# IOmodule-8x_fused_35x25_fm.net
KiCad netlist of a schematic drawn in EAGLE
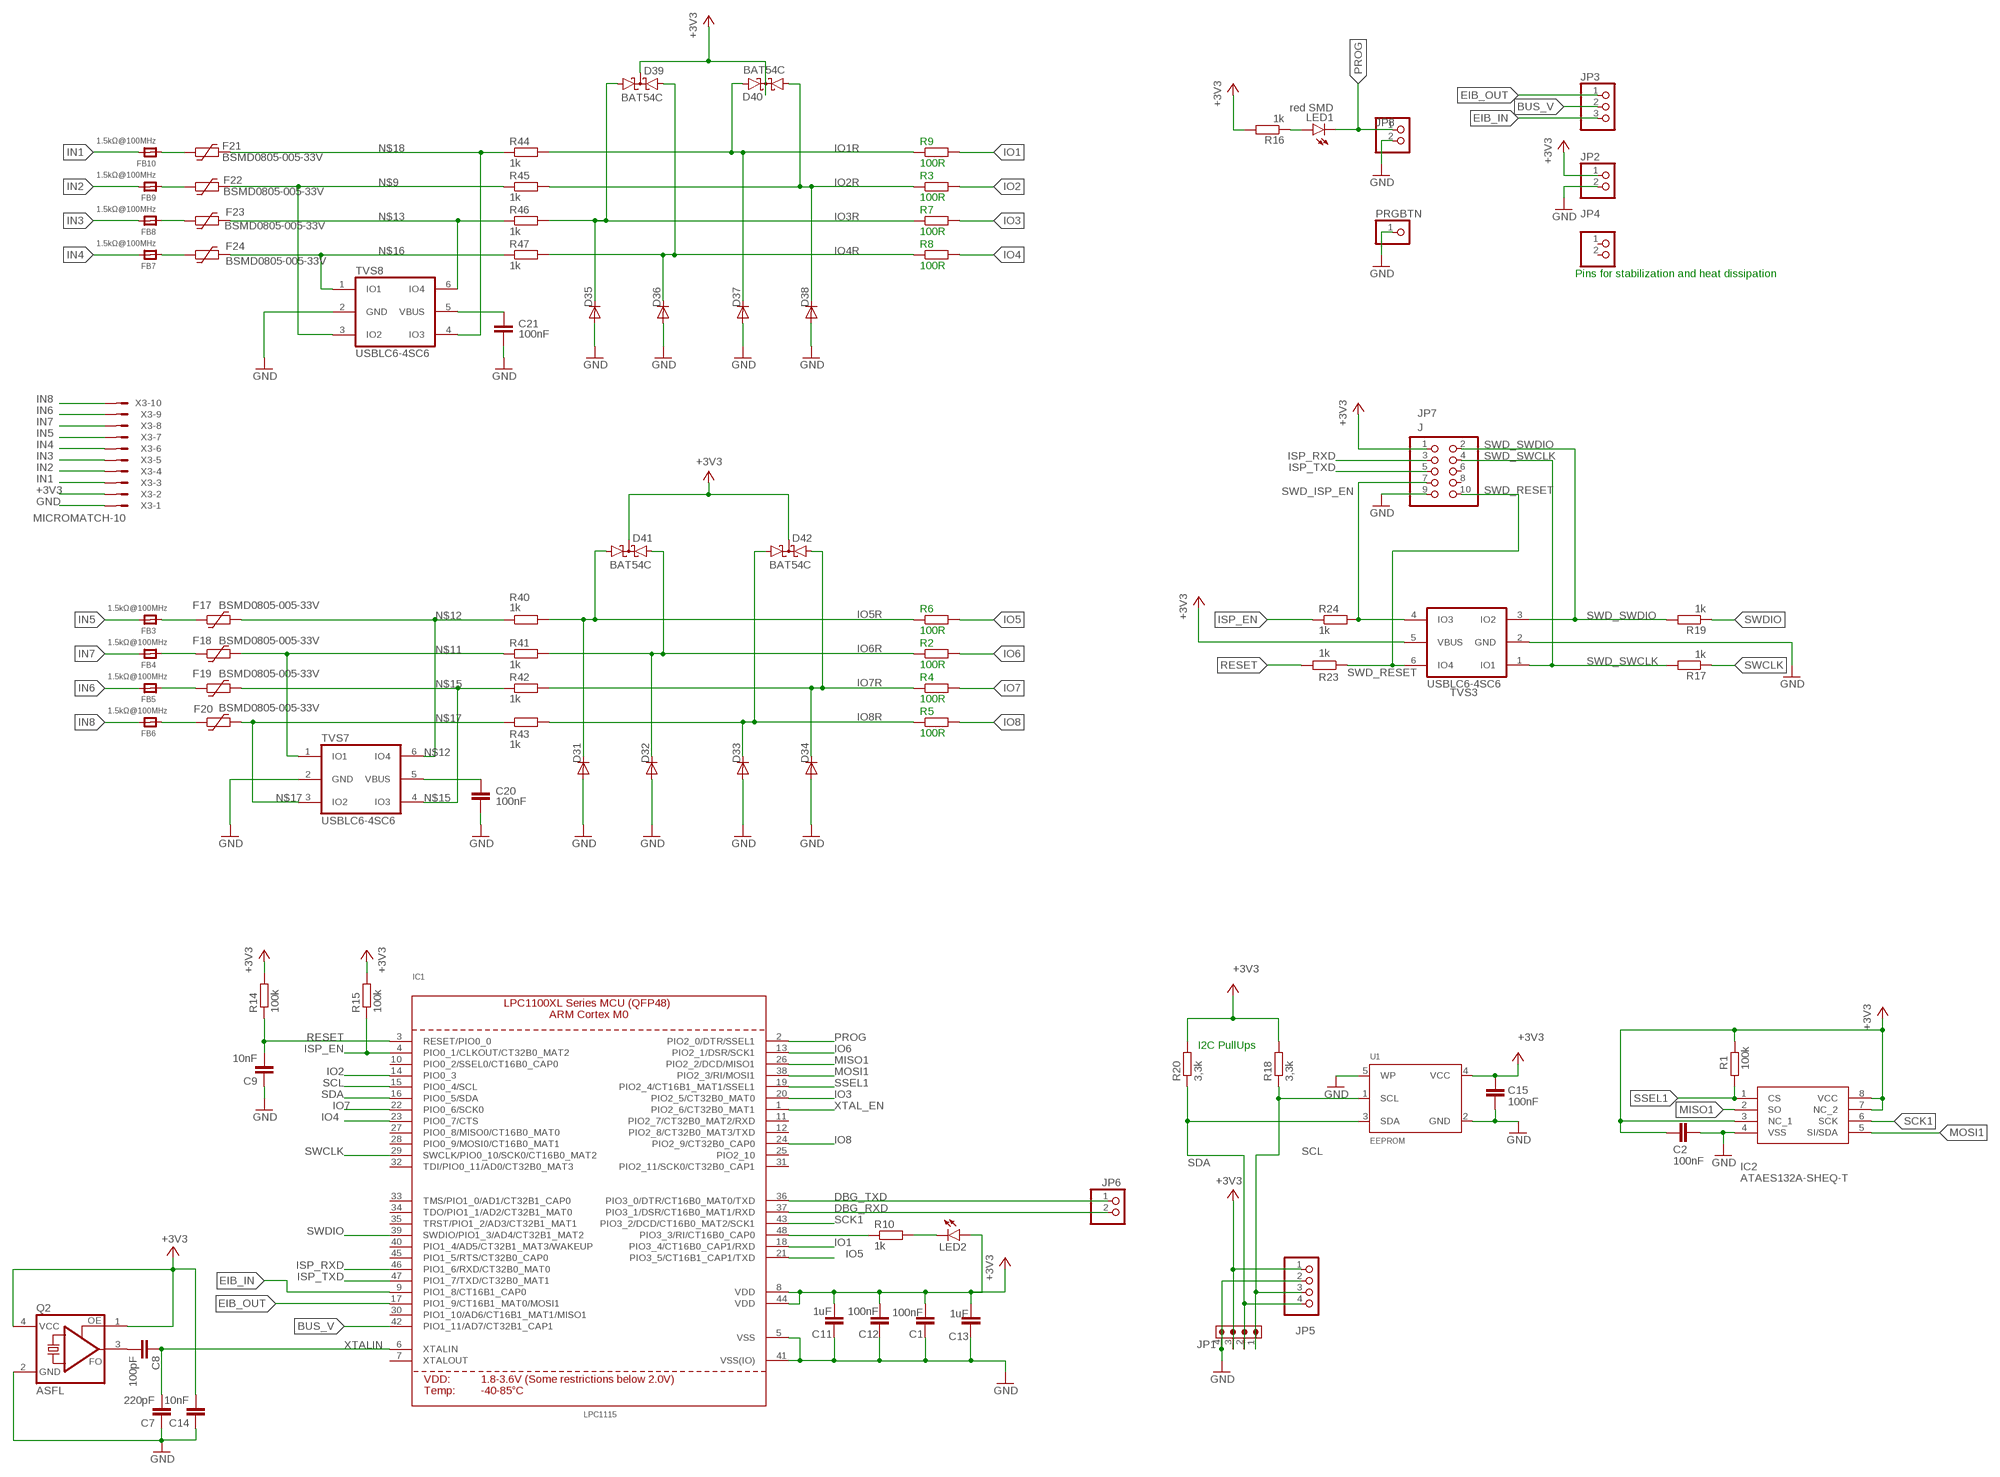
[diagram p0: schematic, sheet 1]

(export (version "E")
  (design (tool "Eeschema 10.0.6"))
  (components
    (comp (ref "C1")
      (value "100nF")
      (footprint "eagle-import:C0805")
      (libsource (lib "eagle-import") (part "C-EUC0805"))
    )
    (comp (ref "C2")
      (value "100nF")
      (footprint "eagle-import:C0805")
      (libsource (lib "eagle-import") (part "C-EUC0805"))
    )
    (comp (ref "C7")
      (value "220pF")
      (footprint "eagle-import:C0805")
      (libsource (lib "eagle-import") (part "C-EUC0805"))
    )
    (comp (ref "C8")
      (value "100pF")
      (footprint "eagle-import:C0805")
      (libsource (lib "eagle-import") (part "C-EUC0805"))
    )
    (comp (ref "C9")
      (value "10nF")
      (footprint "eagle-import:C0805")
      (libsource (lib "eagle-import") (part "C-EUC0805"))
    )
    (comp (ref "C11")
      (value "1uF")
      (footprint "eagle-import:C0805")
      (libsource (lib "eagle-import") (part "C-EUC0805"))
    )
    (comp (ref "C12")
      (value "100nF")
      (footprint "eagle-import:C0805")
      (libsource (lib "eagle-import") (part "C-EUC0805"))
    )
    (comp (ref "C13")
      (value "1uF")
      (footprint "eagle-import:C0805")
      (libsource (lib "eagle-import") (part "C-EUC0805"))
    )
    (comp (ref "C14")
      (value "10nF")
      (footprint "eagle-import:C0805")
      (libsource (lib "eagle-import") (part "C-EUC0805"))
    )
    (comp (ref "C15")
      (value "100nF")
      (footprint "eagle-import:C0805")
      (libsource (lib "eagle-import") (part "C-EUC0805"))
    )
    (comp (ref "C20")
      (value "100nF")
      (footprint "eagle-import:C0805")
      (libsource (lib "eagle-import") (part "C-EUC0805"))
    )
    (comp (ref "C21")
      (value "100nF")
      (footprint "eagle-import:C0805")
      (libsource (lib "eagle-import") (part "C-EUC0805"))
    )
    (comp (ref "D31")
      (value "DDZ9684")
      (footprint "eagle-import:SOD-123")
      (libsource (lib "eagle-import") (part "DIODESOD-123"))
    )
    (comp (ref "D32")
      (value "DDZ9684")
      (footprint "eagle-import:SOD-123")
      (libsource (lib "eagle-import") (part "DIODESOD-123"))
    )
    (comp (ref "D33")
      (value "DDZ9684")
      (footprint "eagle-import:SOD-123")
      (libsource (lib "eagle-import") (part "DIODESOD-123"))
    )
    (comp (ref "D34")
      (value "DDZ9684")
      (footprint "eagle-import:SOD-123")
      (libsource (lib "eagle-import") (part "DIODESOD-123"))
    )
    (comp (ref "D35")
      (value "DDZ9684")
      (footprint "eagle-import:SOD-123")
      (libsource (lib "eagle-import") (part "DIODESOD-123"))
    )
    (comp (ref "D36")
      (value "DDZ9684")
      (footprint "eagle-import:SOD-123")
      (libsource (lib "eagle-import") (part "DIODESOD-123"))
    )
    (comp (ref "D37")
      (value "DDZ9684")
      (footprint "eagle-import:SOD-123")
      (libsource (lib "eagle-import") (part "DIODESOD-123"))
    )
    (comp (ref "D38")
      (value "DDZ9684")
      (footprint "eagle-import:SOD-123")
      (libsource (lib "eagle-import") (part "DIODESOD-123"))
    )
    (comp (ref "D39")
      (value "BAT54C")
      (footprint "eagle-import:SOT23")
      (libsource (lib "eagle-import") (part "BAT54C"))
    )
    (comp (ref "D40")
      (value "BAT54C")
      (footprint "eagle-import:SOT23")
      (libsource (lib "eagle-import") (part "BAT54C"))
    )
    (comp (ref "D41")
      (value "BAT54C")
      (footprint "eagle-import:SOT23")
      (libsource (lib "eagle-import") (part "BAT54C"))
    )
    (comp (ref "D42")
      (value "BAT54C")
      (footprint "eagle-import:SOT23")
      (libsource (lib "eagle-import") (part "BAT54C"))
    )
    (comp (ref "F17")
      (value "BSMD0805-005-33V")
      (footprint "eagle-import:0805L")
      (fields (field (name "MF") "Littelfuse") (field (name "MPN") "0805L035"))
      (libsource (lib "eagle-import") (part "?0805L035"))
    )
    (comp (ref "F18")
      (value "BSMD0805-005-33V")
      (footprint "eagle-import:0805L")
      (fields (field (name "MF") "Littelfuse") (field (name "MPN") "0805L035"))
      (libsource (lib "eagle-import") (part "?0805L035"))
    )
    (comp (ref "F19")
      (value "BSMD0805-005-33V")
      (footprint "eagle-import:0805L")
      (fields (field (name "MF") "Littelfuse") (field (name "MPN") "0805L035"))
      (libsource (lib "eagle-import") (part "?0805L035"))
    )
    (comp (ref "F20")
      (value "BSMD0805-005-33V")
      (footprint "eagle-import:0805L")
      (fields (field (name "MF") "Littelfuse") (field (name "MPN") "0805L035"))
      (libsource (lib "eagle-import") (part "?0805L035"))
    )
    (comp (ref "F21")
      (value "BSMD0805-005-33V")
      (footprint "eagle-import:0805L")
      (fields (field (name "MF") "Littelfuse") (field (name "MPN") "0805L035"))
      (libsource (lib "eagle-import") (part "?0805L035"))
    )
    (comp (ref "F22")
      (value "BSMD0805-005-33V")
      (footprint "eagle-import:0805L")
      (fields (field (name "MF") "Littelfuse") (field (name "MPN") "0805L035"))
      (libsource (lib "eagle-import") (part "?0805L035"))
    )
    (comp (ref "F23")
      (value "BSMD0805-005-33V")
      (footprint "eagle-import:0805L")
      (fields (field (name "MF") "Littelfuse") (field (name "MPN") "0805L035"))
      (libsource (lib "eagle-import") (part "?0805L035"))
    )
    (comp (ref "F24")
      (value "BSMD0805-005-33V")
      (footprint "eagle-import:0805L")
      (fields (field (name "MF") "Littelfuse") (field (name "MPN") "0805L035"))
      (libsource (lib "eagle-import") (part "?0805L035"))
    )
    (comp (ref "FB3")
      (value "1.5kΩ@100MHz")
      (footprint "eagle-import:0805")
      (libsource (lib "eagle-import") (part "FERRITE0805"))
    )
    (comp (ref "FB4")
      (value "1.5kΩ@100MHz")
      (footprint "eagle-import:0805")
      (libsource (lib "eagle-import") (part "FERRITE0805"))
    )
    (comp (ref "FB5")
      (value "1.5kΩ@100MHz")
      (footprint "eagle-import:0805")
      (libsource (lib "eagle-import") (part "FERRITE0805"))
    )
    (comp (ref "FB6")
      (value "1.5kΩ@100MHz")
      (footprint "eagle-import:0805")
      (libsource (lib "eagle-import") (part "FERRITE0805"))
    )
    (comp (ref "FB7")
      (value "1.5kΩ@100MHz")
      (footprint "eagle-import:0805")
      (libsource (lib "eagle-import") (part "FERRITE0805"))
    )
    (comp (ref "FB8")
      (value "1.5kΩ@100MHz")
      (footprint "eagle-import:0805")
      (libsource (lib "eagle-import") (part "FERRITE0805"))
    )
    (comp (ref "FB9")
      (value "1.5kΩ@100MHz")
      (footprint "eagle-import:0805")
      (libsource (lib "eagle-import") (part "FERRITE0805"))
    )
    (comp (ref "FB10")
      (value "1.5kΩ@100MHz")
      (footprint "eagle-import:0805")
      (libsource (lib "eagle-import") (part "FERRITE0805"))
    )
    (comp (ref "IC1")
      (value "LPC1115")
      (footprint "eagle-import:LQFP48")
      (libsource (lib "eagle-import") (part "LPC1113/4/5_QFP48_XLSERIES"))
    )
    (comp (ref "IC2")
      (value "ATAES132A-SHEQ-T")
      (footprint "eagle-import:SOIC127P600X175-8N")
      (fields (field (name "MOUSER_PART_NUMBER") "556-ATAES132A-SHEQ-T"))
      (libsource (lib "eagle-import") (part "ATAES132A-SHEQ-T"))
    )
    (comp (ref "JP1")
      (value "62000411622")
      (footprint "eagle-import:62000411622")
      (libsource (lib "eagle-import") (part "62000411622"))
    )
    (comp (ref "JP2")
      (value "PINHD-1X2")
      (footprint "eagle-import:1X02")
      (libsource (lib "eagle-import") (part "PINHD-1X2"))
    )
    (comp (ref "JP3")
      (value "PINHD-1X3")
      (footprint "eagle-import:1X03")
      (libsource (lib "eagle-import") (part "PINHD-1X3"))
    )
    (comp (ref "JP4")
      (value "PINHD-1X2")
      (footprint "eagle-import:1X02")
      (libsource (lib "eagle-import") (part "PINHD-1X2"))
    )
    (comp (ref "JP5")
      (value "PINHD-1X4")
      (footprint "eagle-import:1X04")
      (libsource (lib "eagle-import") (part "PINHD-1X4"))
    )
    (comp (ref "JP6")
      (value "PINHD-1X2")
      (footprint "eagle-import:1X02")
      (libsource (lib "eagle-import") (part "PINHD-1X2"))
    )
    (comp (ref "JP7")
      (value "J")
      (footprint "eagle-import:2X05M")
      (libsource (lib "eagle-import") (part "PINHD-2X05_2.00"))
    )
    (comp (ref "JP8")
      (value "PINHD-1X2")
      (footprint "eagle-import:1X02")
      (libsource (lib "eagle-import") (part "PINHD-1X2"))
    )
    (comp (ref "LED1")
      (value "red SMD")
      (footprint "eagle-import:CHIPLED_0805")
      (libsource (lib "eagle-import") (part "LEDCHIPLED_0805"))
    )
    (comp (ref "LED2")
      (value "LEDCHIPLED_0805")
      (footprint "eagle-import:CHIPLED_0805")
      (libsource (lib "eagle-import") (part "LEDCHIPLED_0805"))
    )
    (comp (ref "PRGBTN")
      (value "PINHD-1X1")
      (footprint "eagle-import:1X01")
      (libsource (lib "eagle-import") (part "PINHD-1X1"))
    )
    (comp (ref "Q2")
      (value "ASFL")
      (footprint "eagle-import:ASF")
      (fields (field (name "MPN") "ASFLM1-50.000MHZ-C-T"))
      (libsource (lib "eagle-import") (part "ASFL"))
    )
    (comp (ref "R1")
      (value "100k")
      (footprint "eagle-import:R0805")
      (libsource (lib "eagle-import") (part "R-EU_R0805"))
    )
    (comp (ref "R2")
      (value "100R")
      (footprint "eagle-import:R0805")
      (libsource (lib "eagle-import") (part "R-EU_R0805"))
    )
    (comp (ref "R3")
      (value "100R")
      (footprint "eagle-import:R0805")
      (libsource (lib "eagle-import") (part "R-EU_R0805"))
    )
    (comp (ref "R4")
      (value "100R")
      (footprint "eagle-import:R0805")
      (libsource (lib "eagle-import") (part "R-EU_R0805"))
    )
    (comp (ref "R5")
      (value "100R")
      (footprint "eagle-import:R0805")
      (libsource (lib "eagle-import") (part "R-EU_R0805"))
    )
    (comp (ref "R6")
      (value "100R")
      (footprint "eagle-import:R0805")
      (libsource (lib "eagle-import") (part "R-EU_R0805"))
    )
    (comp (ref "R7")
      (value "100R")
      (footprint "eagle-import:R0805")
      (libsource (lib "eagle-import") (part "R-EU_R0805"))
    )
    (comp (ref "R8")
      (value "100R")
      (footprint "eagle-import:R0805")
      (libsource (lib "eagle-import") (part "R-EU_R0805"))
    )
    (comp (ref "R9")
      (value "100R")
      (footprint "eagle-import:R0805")
      (libsource (lib "eagle-import") (part "R-EU_R0805"))
    )
    (comp (ref "R10")
      (value "1k")
      (footprint "eagle-import:R0805")
      (libsource (lib "eagle-import") (part "R-EU_R0805"))
    )
    (comp (ref "R14")
      (value "100k")
      (footprint "eagle-import:R0805")
      (libsource (lib "eagle-import") (part "R-EU_R0805"))
    )
    (comp (ref "R15")
      (value "100k")
      (footprint "eagle-import:R0805")
      (libsource (lib "eagle-import") (part "R-EU_R0805"))
    )
    (comp (ref "R16")
      (value "1k")
      (footprint "eagle-import:R0805")
      (libsource (lib "eagle-import") (part "R-EU_R0805"))
    )
    (comp (ref "R17")
      (value "1k")
      (footprint "eagle-import:R0805")
      (libsource (lib "eagle-import") (part "R-EU_R0805"))
    )
    (comp (ref "R18")
      (value "3,3k")
      (footprint "eagle-import:R0805")
      (libsource (lib "eagle-import") (part "R-EU_R0805"))
    )
    (comp (ref "R19")
      (value "1k")
      (footprint "eagle-import:R0805")
      (libsource (lib "eagle-import") (part "R-EU_R0805"))
    )
    (comp (ref "R20")
      (value "3,3k")
      (footprint "eagle-import:R0805")
      (libsource (lib "eagle-import") (part "R-EU_R0805"))
    )
    (comp (ref "R23")
      (value "1k")
      (footprint "eagle-import:R0805")
      (libsource (lib "eagle-import") (part "R-EU_R0805"))
    )
    (comp (ref "R24")
      (value "1k")
      (footprint "eagle-import:R0805")
      (libsource (lib "eagle-import") (part "R-EU_R0805"))
    )
    (comp (ref "R40")
      (value "1k")
      (footprint "eagle-import:R0805")
      (libsource (lib "eagle-import") (part "R-EU_R0805"))
    )
    (comp (ref "R41")
      (value "1k")
      (footprint "eagle-import:R0805")
      (libsource (lib "eagle-import") (part "R-EU_R0805"))
    )
    (comp (ref "R42")
      (value "1k")
      (footprint "eagle-import:R0805")
      (libsource (lib "eagle-import") (part "R-EU_R0805"))
    )
    (comp (ref "R43")
      (value "1k")
      (footprint "eagle-import:R0805")
      (libsource (lib "eagle-import") (part "R-EU_R0805"))
    )
    (comp (ref "R44")
      (value "1k")
      (footprint "eagle-import:R0805")
      (libsource (lib "eagle-import") (part "R-EU_R0805"))
    )
    (comp (ref "R45")
      (value "1k")
      (footprint "eagle-import:R0805")
      (libsource (lib "eagle-import") (part "R-EU_R0805"))
    )
    (comp (ref "R46")
      (value "1k")
      (footprint "eagle-import:R0805")
      (libsource (lib "eagle-import") (part "R-EU_R0805"))
    )
    (comp (ref "R47")
      (value "1k")
      (footprint "eagle-import:R0805")
      (libsource (lib "eagle-import") (part "R-EU_R0805"))
    )
    (comp (ref "TVS3")
      (value "USBLC6-4SC6")
      (footprint "eagle-import:SOT-23-6L")
      (libsource (lib "eagle-import") (part "USBLC6-4SC6"))
    )
    (comp (ref "TVS7")
      (value "USBLC6-4SC6")
      (footprint "eagle-import:SOT-23-6L")
      (libsource (lib "eagle-import") (part "USBLC6-4SC6"))
    )
    (comp (ref "TVS8")
      (value "USBLC6-4SC6")
      (footprint "eagle-import:SOT-23-6L")
      (libsource (lib "eagle-import") (part "USBLC6-4SC6"))
    )
    (comp (ref "U1")
      (value "EEPROM")
      (footprint "eagle-import:SOT23-5")
      (libsource (lib "eagle-import") (part "EEPROM_I2C_MCP24AA32"))
    )
    (comp (ref "X3")
      (value "MICROMATCH-10")
      (footprint "eagle-import:MICROMATCH-10")
      (fields (field (name "MF") "FARNELL") (field (name "MPN") "8-215464-0"))
      (libsource (lib "eagle-import") (part "MICROMATCH-10"))
    )
  )
  (nets
    (net (code "1") (name "+3V3") (class "Default")
      (node (ref "C1") (pin "2") (pinfunction "2_2") (pintype "passive"))
      (node (ref "C11") (pin "2") (pinfunction "2_2") (pintype "passive"))
      (node (ref "C12") (pin "2") (pinfunction "2_2") (pintype "passive"))
      (node (ref "C13") (pin "2") (pinfunction "2_2") (pintype "passive"))
      (node (ref "C14") (pin "2") (pinfunction "2_2") (pintype "passive"))
      (node (ref "C15") (pin "1") (pinfunction "1_1") (pintype "passive"))
      (node (ref "C2") (pin "1") (pinfunction "1_1") (pintype "passive"))
      (node (ref "D39") (pin "3") (pinfunction "CC_3") (pintype "passive"))
      (node (ref "D40") (pin "3") (pinfunction "CC_3") (pintype "passive"))
      (node (ref "D41") (pin "3") (pinfunction "CC_3") (pintype "passive"))
      (node (ref "D42") (pin "3") (pinfunction "CC_3") (pintype "passive"))
      (node (ref "IC1") (pin "44") (pinfunction "VDD_44") (pintype "power_in"))
      (node (ref "IC1") (pin "8") (pinfunction "VDD_8") (pintype "power_in"))
      (node (ref "IC2") (pin "3") (pinfunction "NC_1_3") (pintype "bidirectional"))
      (node (ref "IC2") (pin "7") (pinfunction "NC_2_7") (pintype "bidirectional"))
      (node (ref "IC2") (pin "8") (pinfunction "VCC_8") (pintype "bidirectional"))
      (node (ref "JP1") (pin "3") (pinfunction "3_3") (pintype "passive"))
      (node (ref "JP2") (pin "1") (pinfunction "1_1") (pintype "passive"))
      (node (ref "JP5") (pin "1") (pinfunction "1_1") (pintype "passive"))
      (node (ref "JP7") (pin "1") (pinfunction "1_1") (pintype "passive"))
      (node (ref "LED2") (pin "A") (pinfunction "A_A") (pintype "passive"))
      (node (ref "Q2") (pin "1") (pinfunction "OE_1") (pintype "input"))
      (node (ref "Q2") (pin "4") (pinfunction "VCC_4") (pintype "power_in"))
      (node (ref "R1") (pin "2") (pinfunction "2_2") (pintype "passive"))
      (node (ref "R14") (pin "2") (pinfunction "2_2") (pintype "passive"))
      (node (ref "R15") (pin "2") (pinfunction "2_2") (pintype "passive"))
      (node (ref "R16") (pin "2") (pinfunction "2_2") (pintype "passive"))
      (node (ref "R18") (pin "2") (pinfunction "2_2") (pintype "passive"))
      (node (ref "R20") (pin "2") (pinfunction "2_2") (pintype "passive"))
      (node (ref "TVS3") (pin "5") (pinfunction "VBUS_5") (pintype "bidirectional"))
      (node (ref "U1") (pin "4") (pinfunction "VCC_4") (pintype "bidirectional"))
      (node (ref "X3") (pin "2") (pinfunction "S_2") (pintype "passive"))
    )
    (net (code "2") (name "/DBG_RXD") (class "Default")
      (node (ref "IC1") (pin "37") (pinfunction "PIO3_1/DSR/CT16B0_MAT1/RXD_37") (pintype "bidirectional"))
      (node (ref "JP6") (pin "2") (pinfunction "2_2") (pintype "passive"))
    )
    (net (code "3") (name "/DBG_TXD") (class "Default")
      (node (ref "IC1") (pin "36") (pinfunction "PIO3_0/DTR/CT16B0_MAT0/TXD_36") (pintype "bidirectional"))
      (node (ref "JP6") (pin "1") (pinfunction "1_1") (pintype "passive"))
    )
    (net (code "4") (name "/IO1R") (class "Default")
      (node (ref "D37") (pin "C") (pinfunction "C_C") (pintype "passive"))
      (node (ref "D40") (pin "2") (pinfunction "A2_2") (pintype "passive"))
      (node (ref "R44") (pin "2") (pinfunction "2_2") (pintype "passive"))
      (node (ref "R9") (pin "1") (pinfunction "1_1") (pintype "passive"))
    )
    (net (code "5") (name "/IO2R") (class "Default")
      (node (ref "D38") (pin "C") (pinfunction "C_C") (pintype "passive"))
      (node (ref "D40") (pin "1") (pinfunction "A1_1") (pintype "passive"))
      (node (ref "R3") (pin "1") (pinfunction "1_1") (pintype "passive"))
      (node (ref "R45") (pin "2") (pinfunction "2_2") (pintype "passive"))
    )
    (net (code "6") (name "/IO3R") (class "Default")
      (node (ref "D35") (pin "C") (pinfunction "C_C") (pintype "passive"))
      (node (ref "D39") (pin "1") (pinfunction "A1_1") (pintype "passive"))
      (node (ref "R46") (pin "2") (pinfunction "2_2") (pintype "passive"))
      (node (ref "R7") (pin "1") (pinfunction "1_1") (pintype "passive"))
    )
    (net (code "7") (name "/IO4R") (class "Default")
      (node (ref "D36") (pin "C") (pinfunction "C_C") (pintype "passive"))
      (node (ref "D39") (pin "2") (pinfunction "A2_2") (pintype "passive"))
      (node (ref "R47") (pin "2") (pinfunction "2_2") (pintype "passive"))
      (node (ref "R8") (pin "1") (pinfunction "1_1") (pintype "passive"))
    )
    (net (code "8") (name "/IO5R") (class "Default")
      (node (ref "D31") (pin "C") (pinfunction "C_C") (pintype "passive"))
      (node (ref "D41") (pin "1") (pinfunction "A1_1") (pintype "passive"))
      (node (ref "R40") (pin "2") (pinfunction "2_2") (pintype "passive"))
      (node (ref "R6") (pin "1") (pinfunction "1_1") (pintype "passive"))
    )
    (net (code "9") (name "/IO6R") (class "Default")
      (node (ref "D32") (pin "C") (pinfunction "C_C") (pintype "passive"))
      (node (ref "D41") (pin "2") (pinfunction "A2_2") (pintype "passive"))
      (node (ref "R2") (pin "1") (pinfunction "1_1") (pintype "passive"))
      (node (ref "R41") (pin "2") (pinfunction "2_2") (pintype "passive"))
    )
    (net (code "10") (name "/IO7R") (class "Default")
      (node (ref "D34") (pin "C") (pinfunction "C_C") (pintype "passive"))
      (node (ref "D42") (pin "2") (pinfunction "A2_2") (pintype "passive"))
      (node (ref "R4") (pin "1") (pinfunction "1_1") (pintype "passive"))
      (node (ref "R42") (pin "2") (pinfunction "2_2") (pintype "passive"))
    )
    (net (code "11") (name "/IO8R") (class "Default")
      (node (ref "D33") (pin "C") (pinfunction "C_C") (pintype "passive"))
      (node (ref "D42") (pin "1") (pinfunction "A1_1") (pintype "passive"))
      (node (ref "R43") (pin "2") (pinfunction "2_2") (pintype "passive"))
      (node (ref "R5") (pin "1") (pinfunction "1_1") (pintype "passive"))
    )
    (net (code "12") (name "/ISP_RXD") (class "Default")
      (node (ref "IC1") (pin "46") (pinfunction "PIO1_6/RXD/CT32B0_MAT0_46") (pintype "bidirectional"))
      (node (ref "JP7") (pin "3") (pinfunction "3_3") (pintype "passive"))
    )
    (net (code "13") (name "/ISP_TXD") (class "Default")
      (node (ref "IC1") (pin "47") (pinfunction "PIO1_7/TXD/CT32B0_MAT1_47") (pintype "bidirectional"))
      (node (ref "JP7") (pin "5") (pinfunction "5_5") (pintype "passive"))
    )
    (net (code "14") (name "/N$9") (class "Default")
      (node (ref "F22") (pin "2") (pinfunction "2_2") (pintype "passive"))
      (node (ref "R45") (pin "1") (pinfunction "1_1") (pintype "passive"))
      (node (ref "TVS8") (pin "3") (pinfunction "IO2_3") (pintype "bidirectional"))
    )
    (net (code "15") (name "/N$11") (class "Default")
      (node (ref "F18") (pin "2") (pinfunction "2_2") (pintype "passive"))
      (node (ref "R41") (pin "1") (pinfunction "1_1") (pintype "passive"))
      (node (ref "TVS7") (pin "1") (pinfunction "IO1_1") (pintype "bidirectional"))
    )
    (net (code "16") (name "/N$12") (class "Default")
      (node (ref "F17") (pin "2") (pinfunction "2_2") (pintype "passive"))
      (node (ref "R40") (pin "1") (pinfunction "1_1") (pintype "passive"))
      (node (ref "TVS7") (pin "6") (pinfunction "IO4_6") (pintype "bidirectional"))
    )
    (net (code "17") (name "/N$13") (class "Default")
      (node (ref "F23") (pin "2") (pinfunction "2_2") (pintype "passive"))
      (node (ref "R46") (pin "1") (pinfunction "1_1") (pintype "passive"))
      (node (ref "TVS8") (pin "6") (pinfunction "IO4_6") (pintype "bidirectional"))
    )
    (net (code "18") (name "/N$15") (class "Default")
      (node (ref "F19") (pin "2") (pinfunction "2_2") (pintype "passive"))
      (node (ref "R42") (pin "1") (pinfunction "1_1") (pintype "passive"))
      (node (ref "TVS7") (pin "4") (pinfunction "IO3_4") (pintype "bidirectional"))
    )
    (net (code "19") (name "/N$16") (class "Default")
      (node (ref "F24") (pin "2") (pinfunction "2_2") (pintype "passive"))
      (node (ref "R47") (pin "1") (pinfunction "1_1") (pintype "passive"))
      (node (ref "TVS8") (pin "1") (pinfunction "IO1_1") (pintype "bidirectional"))
    )
    (net (code "20") (name "/N$17") (class "Default")
      (node (ref "F20") (pin "2") (pinfunction "2_2") (pintype "passive"))
      (node (ref "R43") (pin "1") (pinfunction "1_1") (pintype "passive"))
      (node (ref "TVS7") (pin "3") (pinfunction "IO2_3") (pintype "bidirectional"))
    )
    (net (code "21") (name "/N$18") (class "Default")
      (node (ref "F21") (pin "2") (pinfunction "2_2") (pintype "passive"))
      (node (ref "R44") (pin "1") (pinfunction "1_1") (pintype "passive"))
      (node (ref "TVS8") (pin "4") (pinfunction "IO3_4") (pintype "bidirectional"))
    )
    (net (code "22") (name "/SCL") (class "Default")
      (node (ref "IC1") (pin "15") (pinfunction "PIO0_4/SCL_15") (pintype "bidirectional"))
      (node (ref "JP1") (pin "1") (pinfunction "1_1") (pintype "passive"))
      (node (ref "JP5") (pin "3") (pinfunction "3_3") (pintype "passive"))
      (node (ref "R18") (pin "1") (pinfunction "1_1") (pintype "passive"))
      (node (ref "U1") (pin "1") (pinfunction "SCL_1") (pintype "bidirectional"))
    )
    (net (code "23") (name "/SDA") (class "Default")
      (node (ref "IC1") (pin "16") (pinfunction "PIO0_5/SDA_16") (pintype "bidirectional"))
      (node (ref "JP1") (pin "2") (pinfunction "2_2") (pintype "passive"))
      (node (ref "JP5") (pin "4") (pinfunction "4_4") (pintype "passive"))
      (node (ref "R20") (pin "1") (pinfunction "1_1") (pintype "passive"))
      (node (ref "U1") (pin "3") (pinfunction "SDA_3") (pintype "bidirectional"))
    )
    (net (code "24") (name "/SWD_ISP_EN") (class "Default")
      (node (ref "JP7") (pin "7") (pinfunction "7_7") (pintype "passive"))
      (node (ref "R24") (pin "2") (pinfunction "2_2") (pintype "passive"))
      (node (ref "TVS3") (pin "4") (pinfunction "IO3_4") (pintype "bidirectional"))
    )
    (net (code "25") (name "/SWD_RESET") (class "Default")
      (node (ref "JP7") (pin "10") (pinfunction "10_10") (pintype "passive"))
      (node (ref "R23") (pin "1") (pinfunction "1_1") (pintype "passive"))
      (node (ref "TVS3") (pin "6") (pinfunction "IO4_6") (pintype "bidirectional"))
    )
    (net (code "26") (name "/SWD_SWCLK") (class "Default")
      (node (ref "JP7") (pin "4") (pinfunction "4_4") (pintype "passive"))
      (node (ref "R17") (pin "2") (pinfunction "2_2") (pintype "passive"))
      (node (ref "TVS3") (pin "1") (pinfunction "IO1_1") (pintype "bidirectional"))
    )
    (net (code "27") (name "/SWD_SWDIO") (class "Default")
      (node (ref "JP7") (pin "2") (pinfunction "2_2") (pintype "passive"))
      (node (ref "R19") (pin "2") (pinfunction "2_2") (pintype "passive"))
      (node (ref "TVS3") (pin "3") (pinfunction "IO2_3") (pintype "bidirectional"))
    )
    (net (code "28") (name "/XTALIN") (class "Default")
      (node (ref "C7") (pin "2") (pinfunction "2_2") (pintype "passive"))
      (node (ref "C8") (pin "1") (pinfunction "1_1") (pintype "passive"))
      (node (ref "IC1") (pin "6") (pinfunction "XTALIN_6") (pintype "input"))
    )
    (net (code "29") (name "/XTAL_EN") (class "Default")
      (node (ref "IC1") (pin "1") (pinfunction "PIO2_6/CT32B0_MAT1_1") (pintype "bidirectional"))
    )
    (net (code "30") (name "BUS_V") (class "Default")
      (node (ref "IC1") (pin "42") (pinfunction "PIO1_11/AD7/CT32B1_CAP1_42") (pintype "bidirectional"))
      (node (ref "JP3") (pin "2") (pinfunction "2_2") (pintype "passive"))
    )
    (net (code "31") (name "EIB_IN") (class "Default")
      (node (ref "IC1") (pin "9") (pinfunction "PIO1_8/CT16B1_CAP0_9") (pintype "bidirectional"))
      (node (ref "JP3") (pin "3") (pinfunction "3_3") (pintype "passive"))
    )
    (net (code "32") (name "EIB_OUT") (class "Default")
      (node (ref "IC1") (pin "17") (pinfunction "PIO1_9/CT16B1_MAT0/MOSI1_17") (pintype "bidirectional"))
      (node (ref "JP3") (pin "1") (pinfunction "1_1") (pintype "passive"))
    )
    (net (code "33") (name "GND") (class "Default")
      (node (ref "C1") (pin "1") (pinfunction "1_1") (pintype "passive"))
      (node (ref "C11") (pin "1") (pinfunction "1_1") (pintype "passive"))
      (node (ref "C12") (pin "1") (pinfunction "1_1") (pintype "passive"))
      (node (ref "C13") (pin "1") (pinfunction "1_1") (pintype "passive"))
      (node (ref "C14") (pin "1") (pinfunction "1_1") (pintype "passive"))
      (node (ref "C15") (pin "2") (pinfunction "2_2") (pintype "passive"))
      (node (ref "C2") (pin "2") (pinfunction "2_2") (pintype "passive"))
      (node (ref "C20") (pin "1") (pinfunction "1_1") (pintype "passive"))
      (node (ref "C21") (pin "1") (pinfunction "1_1") (pintype "passive"))
      (node (ref "C7") (pin "1") (pinfunction "1_1") (pintype "passive"))
      (node (ref "C9") (pin "1") (pinfunction "1_1") (pintype "passive"))
      (node (ref "D31") (pin "A") (pinfunction "A_A") (pintype "passive"))
      (node (ref "D32") (pin "A") (pinfunction "A_A") (pintype "passive"))
      (node (ref "D33") (pin "A") (pinfunction "A_A") (pintype "passive"))
      (node (ref "D34") (pin "A") (pinfunction "A_A") (pintype "passive"))
      (node (ref "D35") (pin "A") (pinfunction "A_A") (pintype "passive"))
      (node (ref "D36") (pin "A") (pinfunction "A_A") (pintype "passive"))
      (node (ref "D37") (pin "A") (pinfunction "A_A") (pintype "passive"))
      (node (ref "D38") (pin "A") (pinfunction "A_A") (pintype "passive"))
      (node (ref "IC1") (pin "41") (pinfunction "VSS(IO)_41") (pintype "power_in"))
      (node (ref "IC1") (pin "5") (pinfunction "VSS_5") (pintype "power_in"))
      (node (ref "IC2") (pin "4") (pinfunction "VSS_4") (pintype "bidirectional"))
      (node (ref "JP1") (pin "4") (pinfunction "4_4") (pintype "passive"))
      (node (ref "JP2") (pin "2") (pinfunction "2_2") (pintype "passive"))
      (node (ref "JP5") (pin "2") (pinfunction "2_2") (pintype "passive"))
      (node (ref "JP7") (pin "9") (pinfunction "9_9") (pintype "passive"))
      (node (ref "JP8") (pin "2") (pinfunction "2_2") (pintype "passive"))
      (node (ref "PRGBTN") (pin "1") (pinfunction "1_1") (pintype "passive"))
      (node (ref "Q2") (pin "2") (pinfunction "GND_2") (pintype "power_in"))
      (node (ref "TVS3") (pin "2") (pinfunction "GND_2") (pintype "bidirectional"))
      (node (ref "TVS7") (pin "2") (pinfunction "GND_2") (pintype "bidirectional"))
      (node (ref "TVS8") (pin "2") (pinfunction "GND_2") (pintype "bidirectional"))
      (node (ref "U1") (pin "2") (pinfunction "GND_2") (pintype "bidirectional"))
      (node (ref "U1") (pin "5") (pinfunction "WP_5") (pintype "bidirectional"))
      (node (ref "X3") (pin "1") (pinfunction "S_1") (pintype "passive"))
    )
    (net (code "34") (name "IN1") (class "Default")
      (node (ref "FB10") (pin "2") (pinfunction "P$2_2") (pintype "passive"))
      (node (ref "X3") (pin "3") (pinfunction "S_3") (pintype "passive"))
    )
    (net (code "35") (name "IN2") (class "Default")
      (node (ref "FB9") (pin "2") (pinfunction "P$2_2") (pintype "passive"))
      (node (ref "X3") (pin "4") (pinfunction "S_4") (pintype "passive"))
    )
    (net (code "36") (name "IN3") (class "Default")
      (node (ref "FB8") (pin "2") (pinfunction "P$2_2") (pintype "passive"))
      (node (ref "X3") (pin "5") (pinfunction "S_5") (pintype "passive"))
    )
    (net (code "37") (name "IN4") (class "Default")
      (node (ref "FB7") (pin "2") (pinfunction "P$2_2") (pintype "passive"))
      (node (ref "X3") (pin "6") (pinfunction "S_6") (pintype "passive"))
    )
    (net (code "38") (name "IN5") (class "Default")
      (node (ref "FB3") (pin "2") (pinfunction "P$2_2") (pintype "passive"))
      (node (ref "X3") (pin "7") (pinfunction "S_7") (pintype "passive"))
    )
    (net (code "39") (name "IN6") (class "Default")
      (node (ref "FB5") (pin "2") (pinfunction "P$2_2") (pintype "passive"))
      (node (ref "X3") (pin "9") (pinfunction "S_9") (pintype "passive"))
    )
    (net (code "40") (name "IN7") (class "Default")
      (node (ref "FB4") (pin "2") (pinfunction "P$2_2") (pintype "passive"))
      (node (ref "X3") (pin "8") (pinfunction "S_8") (pintype "passive"))
    )
    (net (code "41") (name "IN8") (class "Default")
      (node (ref "FB6") (pin "2") (pinfunction "P$2_2") (pintype "passive"))
      (node (ref "X3") (pin "10") (pinfunction "S_10") (pintype "passive"))
    )
    (net (code "42") (name "IO1") (class "Default")
      (node (ref "IC1") (pin "18") (pinfunction "PIO3_4/CT16B0_CAP1/RXD_18") (pintype "bidirectional"))
      (node (ref "R9") (pin "2") (pinfunction "2_2") (pintype "passive"))
    )
    (net (code "43") (name "IO2") (class "Default")
      (node (ref "IC1") (pin "14") (pinfunction "PIO0_3_14") (pintype "bidirectional"))
      (node (ref "R3") (pin "2") (pinfunction "2_2") (pintype "passive"))
    )
    (net (code "44") (name "IO3") (class "Default")
      (node (ref "IC1") (pin "20") (pinfunction "PIO2_5/CT32B0_MAT0_20") (pintype "bidirectional"))
      (node (ref "R7") (pin "2") (pinfunction "2_2") (pintype "passive"))
    )
    (net (code "45") (name "IO4") (class "Default")
      (node (ref "IC1") (pin "23") (pinfunction "PIO0_7/CTS_23") (pintype "bidirectional"))
      (node (ref "R8") (pin "2") (pinfunction "2_2") (pintype "passive"))
    )
    (net (code "46") (name "IO5") (class "Default")
      (node (ref "IC1") (pin "21") (pinfunction "PIO3_5/CT16B1_CAP1/TXD_21") (pintype "bidirectional"))
      (node (ref "R6") (pin "2") (pinfunction "2_2") (pintype "passive"))
    )
    (net (code "47") (name "IO6") (class "Default")
      (node (ref "IC1") (pin "13") (pinfunction "PIO2_1/DSR/SCK1_13") (pintype "bidirectional"))
      (node (ref "R2") (pin "2") (pinfunction "2_2") (pintype "passive"))
    )
    (net (code "48") (name "IO7") (class "Default")
      (node (ref "IC1") (pin "22") (pinfunction "PIO0_6/SCK0_22") (pintype "bidirectional"))
      (node (ref "R4") (pin "2") (pinfunction "2_2") (pintype "passive"))
    )
    (net (code "49") (name "IO8") (class "Default")
      (node (ref "IC1") (pin "24") (pinfunction "PIO2_9/CT32B0_CAP0_24") (pintype "bidirectional"))
      (node (ref "R5") (pin "2") (pinfunction "2_2") (pintype "passive"))
    )
    (net (code "50") (name "ISP_EN") (class "Default")
      (node (ref "IC1") (pin "4") (pinfunction "PIO0_1/CLKOUT/CT32B0_MAT2_4") (pintype "bidirectional"))
      (node (ref "R15") (pin "1") (pinfunction "1_1") (pintype "passive"))
      (node (ref "R24") (pin "1") (pinfunction "1_1") (pintype "passive"))
    )
    (net (code "51") (name "MISO1") (class "Default")
      (node (ref "IC1") (pin "26") (pinfunction "PIO2_2/DCD/MISO1_26") (pintype "bidirectional"))
      (node (ref "IC2") (pin "2") (pinfunction "SO_2") (pintype "bidirectional"))
    )
    (net (code "52") (name "MOSI1") (class "Default")
      (node (ref "IC1") (pin "38") (pinfunction "PIO2_3/RI/MOSI1_38") (pintype "bidirectional"))
      (node (ref "IC2") (pin "5") (pinfunction "SI/SDA_5") (pintype "bidirectional"))
    )
    (net (code "53") (name "Net-(FB3-P$1)") (class "Default")
      (node (ref "F17") (pin "1") (pinfunction "1_1") (pintype "passive"))
      (node (ref "FB3") (pin "1") (pinfunction "P$1_1") (pintype "passive"))
    )
    (net (code "54") (name "Net-(FB4-P$1)") (class "Default")
      (node (ref "F18") (pin "1") (pinfunction "1_1") (pintype "passive"))
      (node (ref "FB4") (pin "1") (pinfunction "P$1_1") (pintype "passive"))
    )
    (net (code "55") (name "Net-(FB5-P$1)") (class "Default")
      (node (ref "F19") (pin "1") (pinfunction "1_1") (pintype "passive"))
      (node (ref "FB5") (pin "1") (pinfunction "P$1_1") (pintype "passive"))
    )
    (net (code "56") (name "Net-(FB6-P$1)") (class "Default")
      (node (ref "F20") (pin "1") (pinfunction "1_1") (pintype "passive"))
      (node (ref "FB6") (pin "1") (pinfunction "P$1_1") (pintype "passive"))
    )
    (net (code "57") (name "Net-(FB7-P$1)") (class "Default")
      (node (ref "F24") (pin "1") (pinfunction "1_1") (pintype "passive"))
      (node (ref "FB7") (pin "1") (pinfunction "P$1_1") (pintype "passive"))
    )
    (net (code "58") (name "Net-(FB8-P$1)") (class "Default")
      (node (ref "F23") (pin "1") (pinfunction "1_1") (pintype "passive"))
      (node (ref "FB8") (pin "1") (pinfunction "P$1_1") (pintype "passive"))
    )
    (net (code "59") (name "Net-(FB9-P$1)") (class "Default")
      (node (ref "F22") (pin "1") (pinfunction "1_1") (pintype "passive"))
      (node (ref "FB9") (pin "1") (pinfunction "P$1_1") (pintype "passive"))
    )
    (net (code "60") (name "Net-(FB10-P$1)") (class "Default")
      (node (ref "F21") (pin "1") (pinfunction "1_1") (pintype "passive"))
      (node (ref "FB10") (pin "1") (pinfunction "P$1_1") (pintype "passive"))
    )
    (net (code "61") (name "Net-(IC1-PIO3_3{slash}RI{slash}CT16B0_CAP0)") (class "Default")
      (node (ref "IC1") (pin "48") (pinfunction "PIO3_3/RI/CT16B0_CAP0_48") (pintype "bidirectional"))
      (node (ref "R10") (pin "1") (pinfunction "1_1") (pintype "passive"))
    )
    (net (code "62") (name "Net-(LED1-PadA)") (class "Default")
      (node (ref "LED1") (pin "A") (pinfunction "A_A") (pintype "passive"))
      (node (ref "R16") (pin "1") (pinfunction "1_1") (pintype "passive"))
    )
    (net (code "63") (name "Net-(LED2-PadC)") (class "Default")
      (node (ref "LED2") (pin "C") (pinfunction "C_C") (pintype "passive"))
      (node (ref "R10") (pin "2") (pinfunction "2_2") (pintype "passive"))
    )
    (net (code "64") (name "Net-(Q2-FO)") (class "Default")
      (node (ref "C8") (pin "2") (pinfunction "2_2") (pintype "passive"))
      (node (ref "Q2") (pin "3") (pinfunction "FO_3") (pintype "output"))
    )
    (net (code "65") (name "Net-(TVS7-VBUS)") (class "Default")
      (node (ref "C20") (pin "2") (pinfunction "2_2") (pintype "passive"))
      (node (ref "TVS7") (pin "5") (pinfunction "VBUS_5") (pintype "bidirectional"))
    )
    (net (code "66") (name "Net-(TVS8-VBUS)") (class "Default")
      (node (ref "C21") (pin "2") (pinfunction "2_2") (pintype "passive"))
      (node (ref "TVS8") (pin "5") (pinfunction "VBUS_5") (pintype "bidirectional"))
    )
    (net (code "67") (name "PROG") (class "Default")
      (node (ref "IC1") (pin "2") (pinfunction "PIO2_0/DTR/SSEL1_2") (pintype "bidirectional"))
      (node (ref "JP8") (pin "1") (pinfunction "1_1") (pintype "passive"))
      (node (ref "LED1") (pin "C") (pinfunction "C_C") (pintype "passive"))
    )
    (net (code "68") (name "RESET") (class "Default")
      (node (ref "C9") (pin "2") (pinfunction "2_2") (pintype "passive"))
      (node (ref "IC1") (pin "3") (pinfunction "RESET/PIO0_0_3") (pintype "bidirectional"))
      (node (ref "R14") (pin "1") (pinfunction "1_1") (pintype "passive"))
      (node (ref "R23") (pin "2") (pinfunction "2_2") (pintype "passive"))
    )
    (net (code "69") (name "SCK1") (class "Default")
      (node (ref "IC1") (pin "43") (pinfunction "PIO3_2/DCD/CT16B0_MAT2/SCK1_43") (pintype "bidirectional"))
      (node (ref "IC2") (pin "6") (pinfunction "SCK_6") (pintype "bidirectional"))
    )
    (net (code "70") (name "SSEL1") (class "Default")
      (node (ref "IC1") (pin "19") (pinfunction "PIO2_4/CT16B1_MAT1/SSEL1_19") (pintype "bidirectional"))
      (node (ref "IC2") (pin "1") (pinfunction "CS_1") (pintype "bidirectional"))
      (node (ref "R1") (pin "1") (pinfunction "1_1") (pintype "passive"))
    )
    (net (code "71") (name "SWCLK") (class "Default")
      (node (ref "IC1") (pin "29") (pinfunction "SWCLK/PIO0_10/SCK0/CT16B0_MAT2_29") (pintype "bidirectional"))
      (node (ref "R17") (pin "1") (pinfunction "1_1") (pintype "passive"))
    )
    (net (code "72") (name "SWDIO") (class "Default")
      (node (ref "IC1") (pin "39") (pinfunction "SWDIO/PIO1_3/AD4/CT32B1_MAT2_39") (pintype "bidirectional"))
      (node (ref "R19") (pin "1") (pinfunction "1_1") (pintype "passive"))
    )
    (net (code "73") (name "unconnected-(IC1-PIO0_2{slash}SSEL0{slash}CT16B0_CAP0-Pad10)") (class "Default")
      (node (ref "IC1") (pin "10") (pinfunction "PIO0_2/SSEL0/CT16B0_CAP0_10") (pintype "bidirectional"))
    )
    (net (code "74") (name "unconnected-(IC1-PIO0_8{slash}MISO0{slash}CT16B0_MAT0-Pad27)") (class "Default")
      (node (ref "IC1") (pin "27") (pinfunction "PIO0_8/MISO0/CT16B0_MAT0_27") (pintype "bidirectional"))
    )
    (net (code "75") (name "unconnected-(IC1-PIO0_9{slash}MOSI0{slash}CT16B0_MAT1-Pad28)") (class "Default")
      (node (ref "IC1") (pin "28") (pinfunction "PIO0_9/MOSI0/CT16B0_MAT1_28") (pintype "bidirectional"))
    )
    (net (code "76") (name "unconnected-(IC1-PIO1_4{slash}AD5{slash}CT32B1_MAT3{slash}WAKEUP-Pad40)") (class "Default")
      (node (ref "IC1") (pin "40") (pinfunction "PIO1_4/AD5/CT32B1_MAT3/WAKEUP_40") (pintype "bidirectional"))
    )
    (net (code "77") (name "unconnected-(IC1-PIO1_5{slash}RTS{slash}CT32B0_CAP0-Pad45)") (class "Default")
      (node (ref "IC1") (pin "45") (pinfunction "PIO1_5/RTS/CT32B0_CAP0_45") (pintype "bidirectional"))
    )
    (net (code "78") (name "unconnected-(IC1-PIO1_10{slash}AD6{slash}CT16B1_MAT1{slash}MISO1-Pad30)") (class "Default")
      (node (ref "IC1") (pin "30") (pinfunction "PIO1_10/AD6/CT16B1_MAT1/MISO1_30") (pintype "bidirectional"))
    )
    (net (code "79") (name "unconnected-(IC1-PIO2_7{slash}CT32B0_MAT2{slash}RXD-Pad11)") (class "Default")
      (node (ref "IC1") (pin "11") (pinfunction "PIO2_7/CT32B0_MAT2/RXD_11") (pintype "bidirectional"))
    )
    (net (code "80") (name "unconnected-(IC1-PIO2_8{slash}CT32B0_MAT3{slash}TXD-Pad12)") (class "Default")
      (node (ref "IC1") (pin "12") (pinfunction "PIO2_8/CT32B0_MAT3/TXD_12") (pintype "bidirectional"))
    )
    (net (code "81") (name "unconnected-(IC1-PIO2_10-Pad25)") (class "Default")
      (node (ref "IC1") (pin "25") (pinfunction "PIO2_10_25") (pintype "bidirectional"))
    )
    (net (code "82") (name "unconnected-(IC1-PIO2_11{slash}SCK0{slash}CT32B0_CAP1-Pad31)") (class "Default")
      (node (ref "IC1") (pin "31") (pinfunction "PIO2_11/SCK0/CT32B0_CAP1_31") (pintype "bidirectional"))
    )
    (net (code "83") (name "unconnected-(IC1-TDI{slash}PIO0_11{slash}AD0{slash}CT32B0_MAT3-Pad32)") (class "Default")
      (node (ref "IC1") (pin "32") (pinfunction "TDI/PIO0_11/AD0/CT32B0_MAT3_32") (pintype "bidirectional"))
    )
    (net (code "84") (name "unconnected-(IC1-TDO{slash}PIO1_1{slash}AD2{slash}CT32B1_MAT0-Pad34)") (class "Default")
      (node (ref "IC1") (pin "34") (pinfunction "TDO/PIO1_1/AD2/CT32B1_MAT0_34") (pintype "bidirectional"))
    )
    (net (code "85") (name "unconnected-(IC1-TMS{slash}PIO1_0{slash}AD1{slash}CT32B1_CAP0-Pad33)") (class "Default")
      (node (ref "IC1") (pin "33") (pinfunction "TMS/PIO1_0/AD1/CT32B1_CAP0_33") (pintype "bidirectional"))
    )
    (net (code "86") (name "unconnected-(IC1-TRST{slash}PIO1_2{slash}AD3{slash}CT32B1_MAT1-Pad35)") (class "Default")
      (node (ref "IC1") (pin "35") (pinfunction "TRST/PIO1_2/AD3/CT32B1_MAT1_35") (pintype "bidirectional"))
    )
    (net (code "87") (name "unconnected-(IC1-XTALOUT-Pad7)") (class "Default")
      (node (ref "IC1") (pin "7") (pinfunction "XTALOUT_7") (pintype "output"))
    )
    (net (code "88") (name "unconnected-(JP4-Pad1)") (class "Default")
      (node (ref "JP4") (pin "1") (pinfunction "1_1") (pintype "passive"))
    )
    (net (code "89") (name "unconnected-(JP4-Pad2)") (class "Default")
      (node (ref "JP4") (pin "2") (pinfunction "2_2") (pintype "passive"))
    )
    (net (code "90") (name "unconnected-(JP7-Pad6)") (class "Default")
      (node (ref "JP7") (pin "6") (pinfunction "6_6") (pintype "passive"))
    )
    (net (code "91") (name "unconnected-(JP7-Pad8)") (class "Default")
      (node (ref "JP7") (pin "8") (pinfunction "8_8") (pintype "passive"))
    )
  )
)
